# module_instr_reg.net
KiCad netlist of a schematic drawn in EAGLE
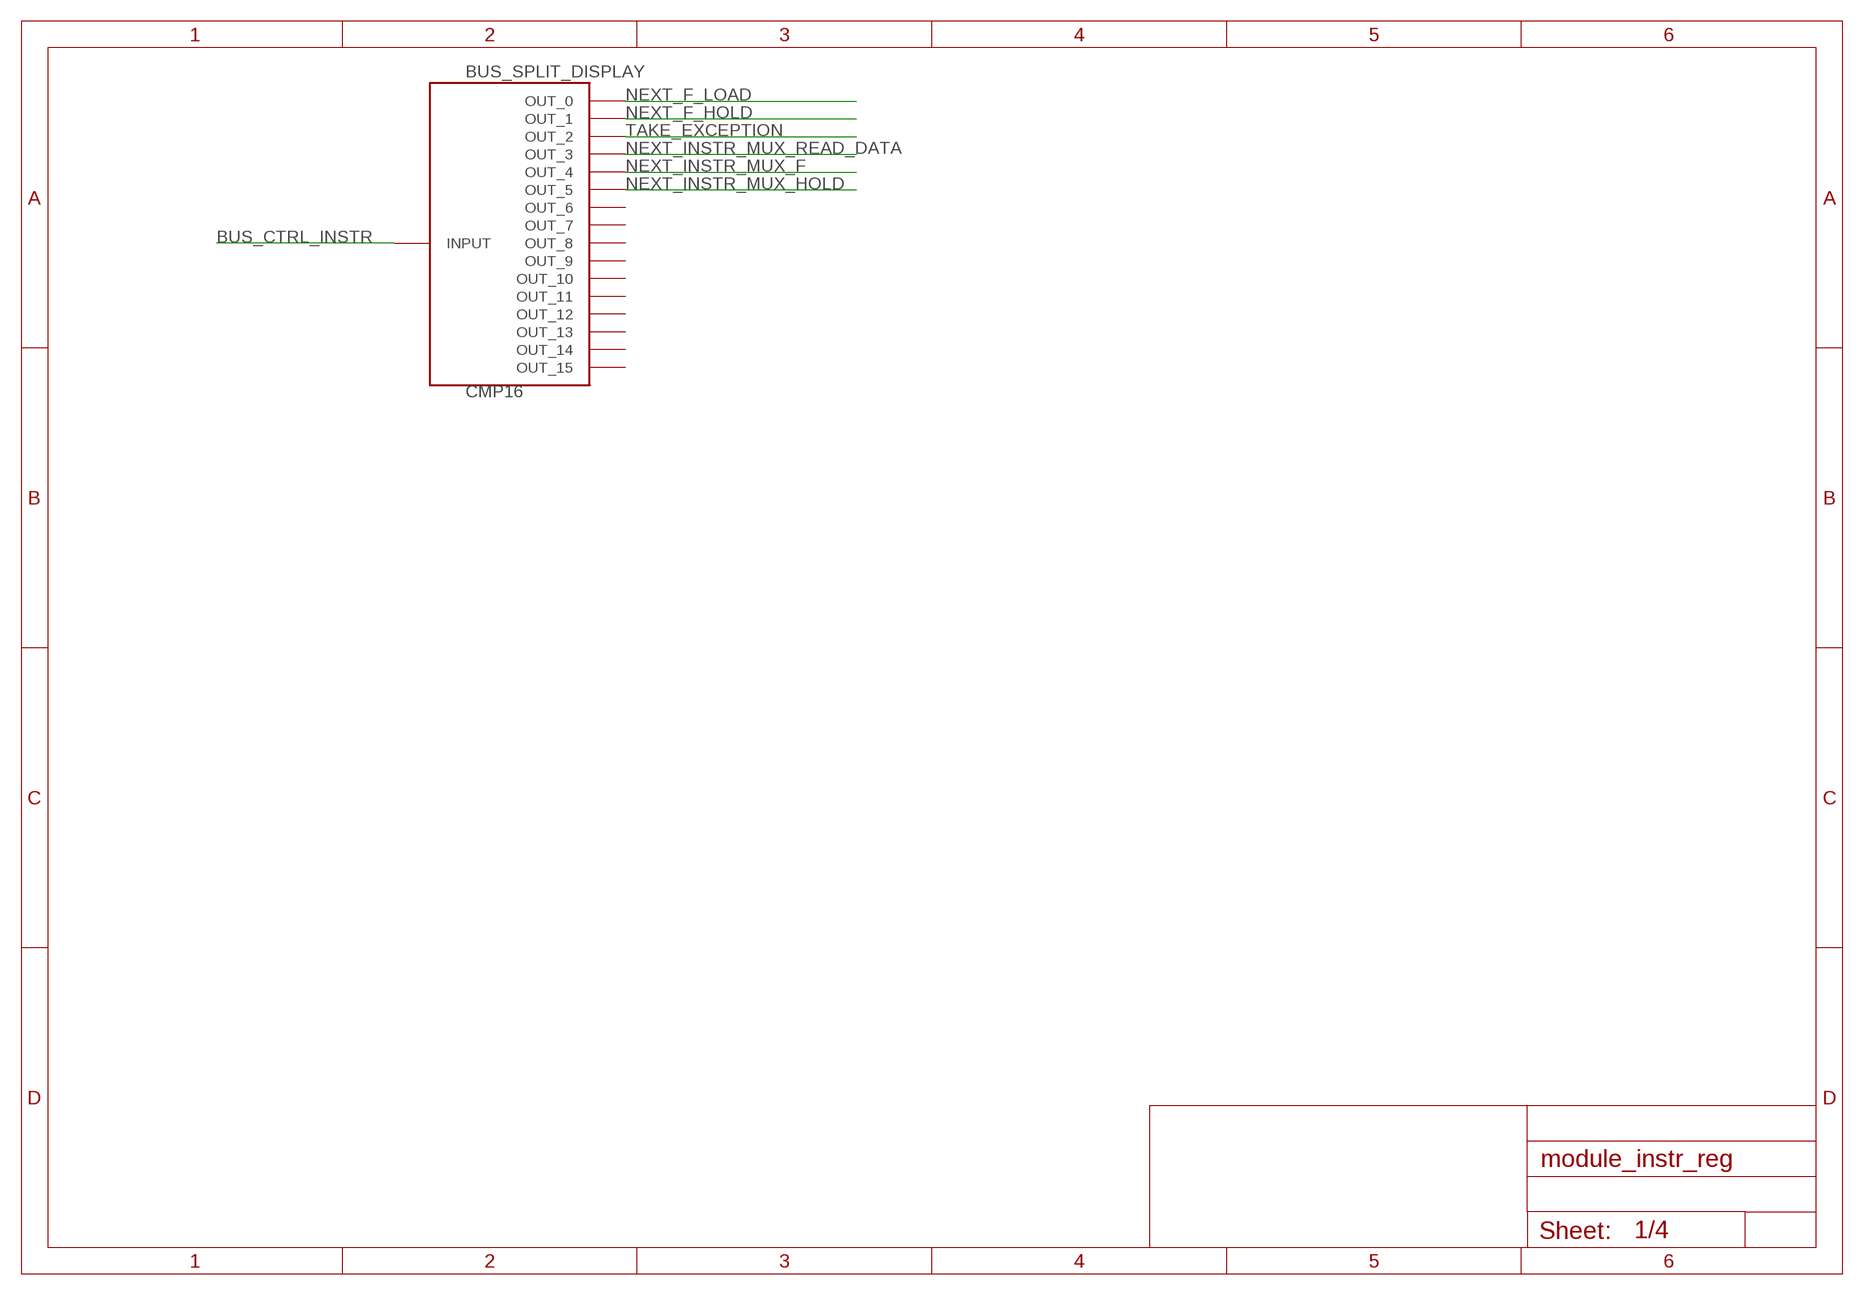
[diagram p0: schematic, sheet 1]
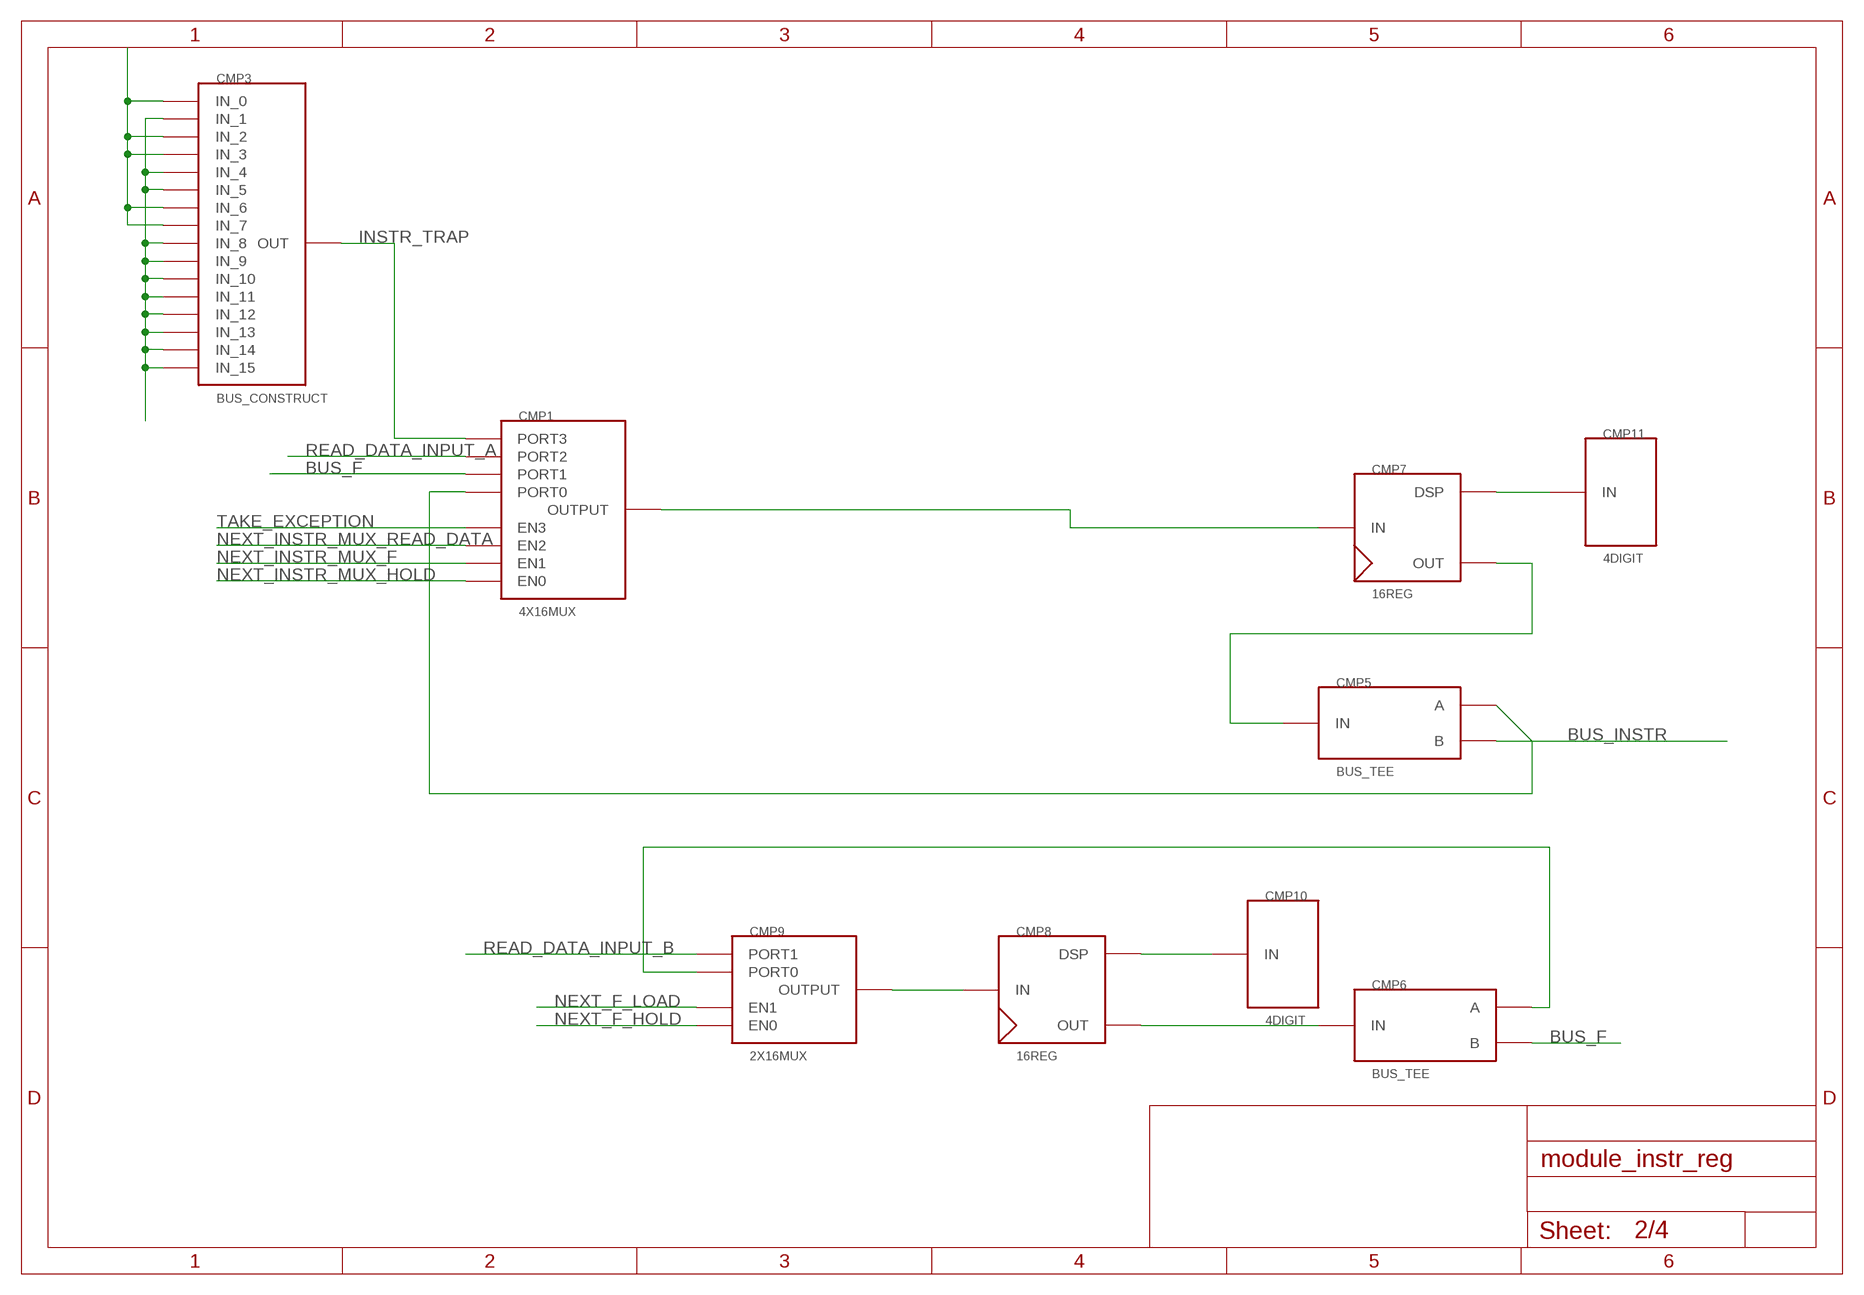
[diagram p1: schematic, sheet 2]
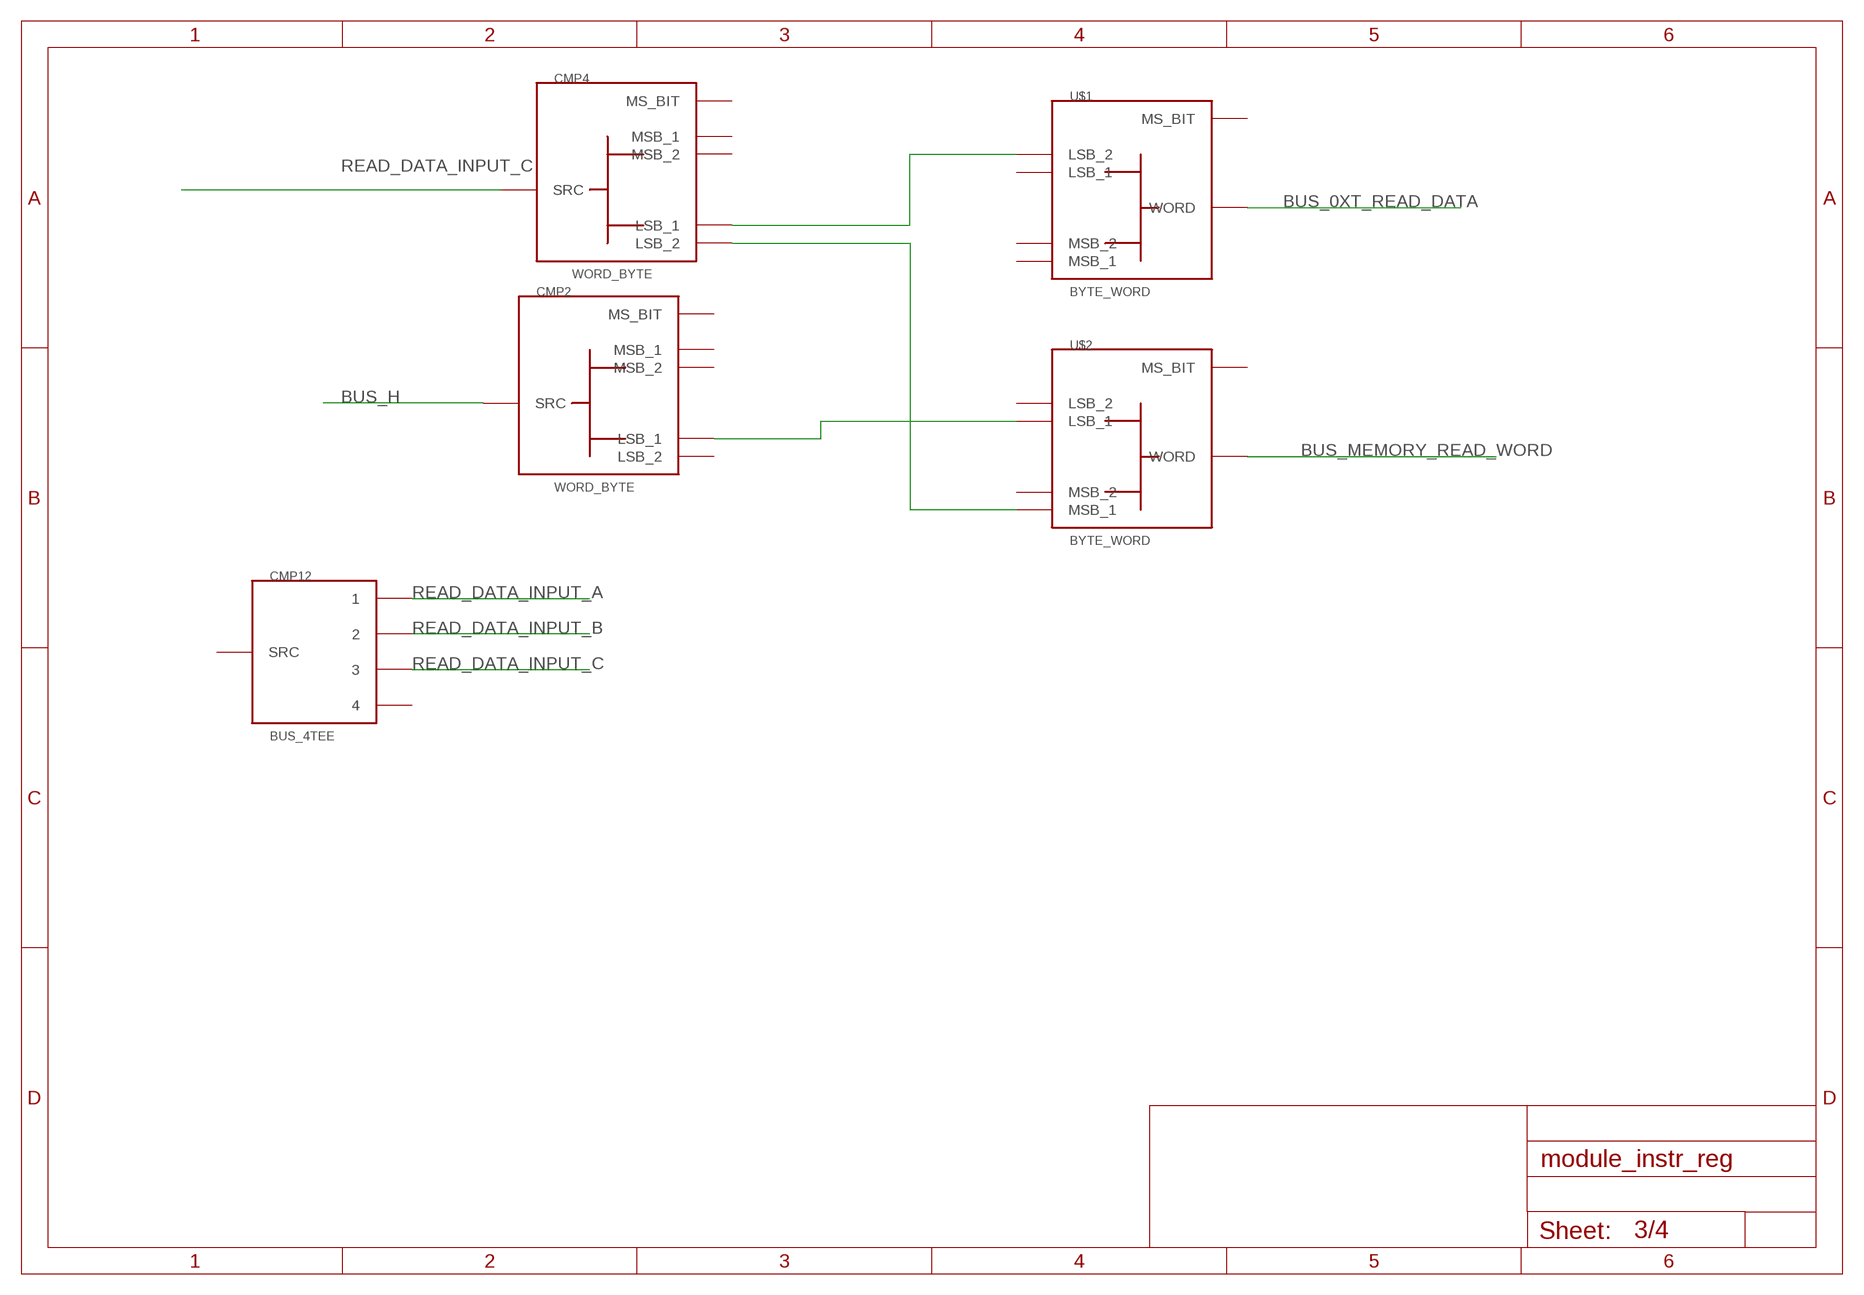
[diagram p2: schematic, sheet 3]
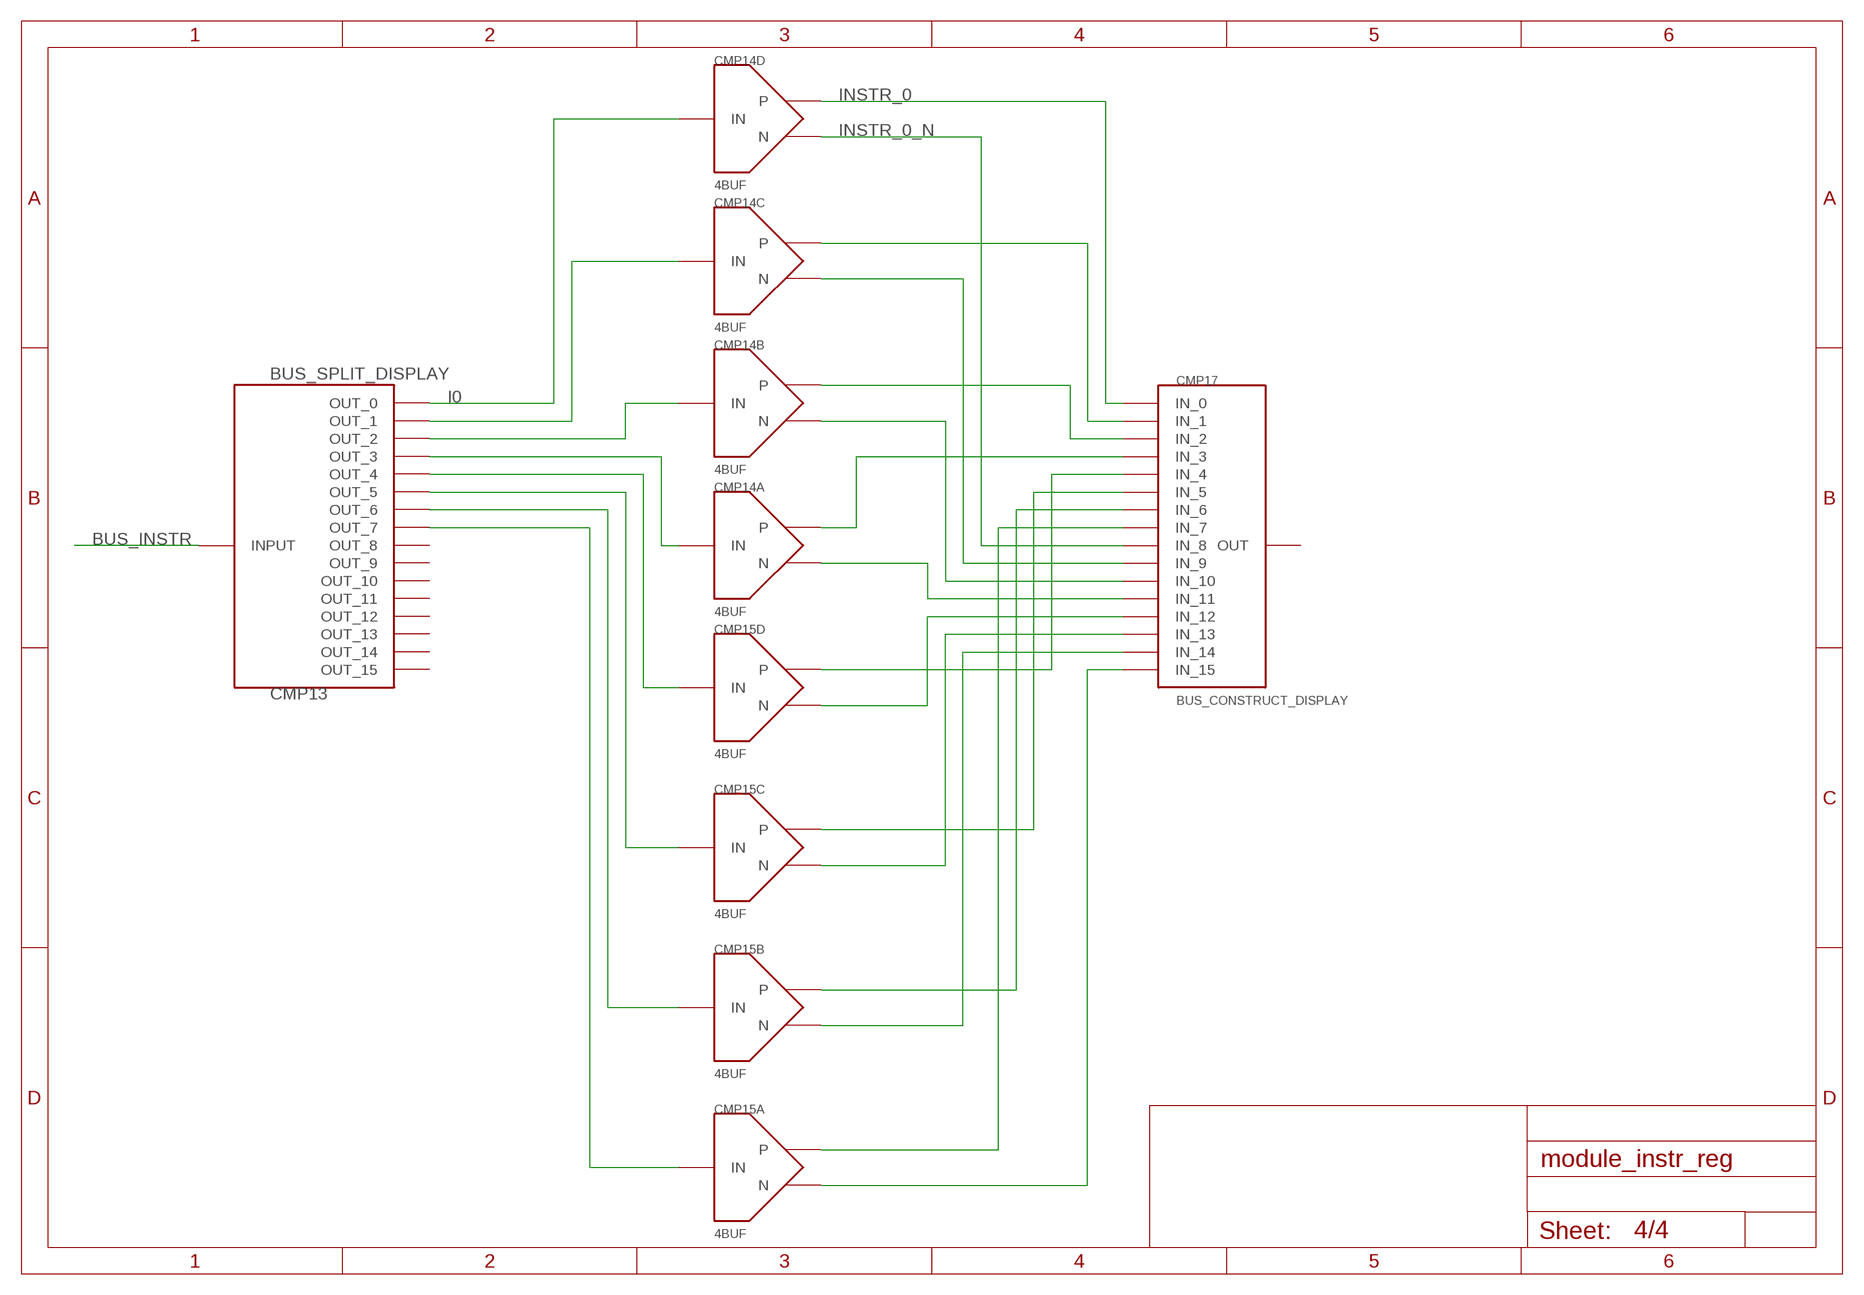
[diagram p3: schematic, sheet 4]

(export (version "E")
  (design (tool "Eeschema 10.0.6"))
  (components
    (comp (ref "CMP16")
      (value "BUS_SPLIT_DISPLAY")
      (footprint "eagle-import:BUS_SPLIT_DISPLAY")
      (libsource (lib "eagle-import") (part "BUS_SPLIT_DISPLAY"))
    )
    (comp (ref "CMP1")
      (value "4X16MUX")
      (footprint "eagle-import:4X16MUX")
      (libsource (lib "eagle-import") (part "4X16MUX"))
    )
    (comp (ref "CMP3")
      (value "BUS_CONSTRUCT")
      (footprint "eagle-import:BUS_SPLIT")
      (libsource (lib "eagle-import") (part "BUS_CONSTRUCT"))
    )
    (comp (ref "CMP5")
      (value "BUS_TEE")
      (footprint "eagle-import:BUS_TEE")
      (libsource (lib "eagle-import") (part "BUS_TEE"))
    )
    (comp (ref "CMP6")
      (value "BUS_TEE")
      (footprint "eagle-import:BUS_TEE")
      (libsource (lib "eagle-import") (part "BUS_TEE"))
    )
    (comp (ref "CMP7")
      (value "16REG")
      (footprint "eagle-import:16REG")
      (libsource (lib "eagle-import") (part "16REG"))
    )
    (comp (ref "CMP8")
      (value "16REG")
      (footprint "eagle-import:16REG")
      (libsource (lib "eagle-import") (part "16REG"))
    )
    (comp (ref "CMP9")
      (value "2X16MUX")
      (footprint "eagle-import:2X16MUX")
      (libsource (lib "eagle-import") (part "2X16MUX"))
    )
    (comp (ref "CMP10")
      (value "4DIGIT")
      (footprint "eagle-import:4DIGIT")
      (libsource (lib "eagle-import") (part "4DIGIT"))
    )
    (comp (ref "CMP11")
      (value "4DIGIT")
      (footprint "eagle-import:4DIGIT")
      (libsource (lib "eagle-import") (part "4DIGIT"))
    )
    (comp (ref "CMP2")
      (value "WORD_BYTE")
      (footprint "eagle-import:WORD_BYTE")
      (libsource (lib "eagle-import") (part "WORD_BYTE"))
    )
    (comp (ref "CMP4")
      (value "WORD_BYTE")
      (footprint "eagle-import:WORD_BYTE")
      (libsource (lib "eagle-import") (part "WORD_BYTE"))
    )
    (comp (ref "CMP12")
      (value "BUS_4TEE")
      (footprint "eagle-import:BUS_4TEE")
      (libsource (lib "eagle-import") (part "BUS_4TEE"))
    )
    (comp (ref "U$1")
      (value "BYTE_WORD")
      (footprint "eagle-import:WORD_BYTE")
      (libsource (lib "eagle-import") (part "BYTE_WORD"))
    )
    (comp (ref "U$2")
      (value "BYTE_WORD")
      (footprint "eagle-import:WORD_BYTE")
      (libsource (lib "eagle-import") (part "BYTE_WORD"))
    )
    (comp (ref "CMP13")
      (value "BUS_SPLIT_DISPLAY")
      (footprint "eagle-import:BUS_SPLIT_DISPLAY")
      (libsource (lib "eagle-import") (part "BUS_SPLIT_DISPLAY"))
    )
    (comp (ref "CMP14")
      (value "4BUF")
      (footprint "eagle-import:4BUF")
      (libsource (lib "eagle-import") (part "4BUF"))
    )
    (comp (ref "CMP15")
      (value "4BUF")
      (footprint "eagle-import:4BUF")
      (libsource (lib "eagle-import") (part "4BUF"))
    )
    (comp (ref "CMP17")
      (value "BUS_CONSTRUCT_DISPLAY")
      (footprint "eagle-import:BUS_SPLIT_DISPLAY")
      (libsource (lib "eagle-import") (part "BUS_CONSTRUCT_DISPLAY"))
    )
  )
  (nets
    (net (code "1") (name "BUS_0XT_READ_DATA") (class "Default")
      (node (ref "U$1") (pin "SRC") (pinfunction "WORD_SRC") (pintype "output"))
    )
    (net (code "2") (name "BUS_CTRL_INSTR") (class "Default")
      (node (ref "CMP16") (pin "INPUT") (pinfunction "INPUT_INPUT") (pintype "input"))
    )
    (net (code "3") (name "BUS_F") (class "Default")
      (node (ref "CMP1") (pin "PORT1") (pinfunction "PORT1_PORT1") (pintype "input"))
      (node (ref "CMP6") (pin "OUTB") (pinfunction "B_OUTB") (pintype "output"))
    )
    (net (code "4") (name "BUS_H") (class "Default")
      (node (ref "CMP2") (pin "SRC") (pinfunction "SRC_SRC") (pintype "input"))
    )
    (net (code "5") (name "BUS_INSTR") (class "Default")
      (node (ref "CMP13") (pin "INPUT") (pinfunction "INPUT_INPUT") (pintype "input"))
      (node (ref "CMP5") (pin "OUTB") (pinfunction "B_OUTB") (pintype "output"))
    )
    (net (code "6") (name "BUS_MEMORY_READ_WORD") (class "Default")
      (node (ref "U$2") (pin "SRC") (pinfunction "WORD_SRC") (pintype "output"))
    )
    (net (code "7") (name "I0") (class "Default")
      (node (ref "CMP13") (pin "P$1") (pinfunction "OUT_0_P$1") (pintype "output"))
      (node (ref "CMP14") (pin "A4") (pinfunction "IN_A4") (pintype "input"))
    )
    (net (code "8") (name "INSTR_0") (class "Default")
      (node (ref "CMP14") (pin "P4") (pinfunction "P_P4") (pintype "output"))
      (node (ref "CMP17") (pin "P$1") (pinfunction "IN_0_P$1") (pintype "input"))
    )
    (net (code "9") (name "INSTR_0_N") (class "Default")
      (node (ref "CMP14") (pin "N4") (pinfunction "N_N4") (pintype "output"))
      (node (ref "CMP17") (pin "P$9") (pinfunction "IN_8_P$9") (pintype "input"))
    )
    (net (code "10") (name "INSTR_TRAP") (class "Default")
      (node (ref "CMP1") (pin "PORT3") (pinfunction "PORT3_PORT3") (pintype "input"))
      (node (ref "CMP3") (pin "INPUT") (pinfunction "OUT_INPUT") (pintype "output"))
    )
    (net (code "11") (name "NEXT_F_HOLD") (class "Default")
      (node (ref "CMP16") (pin "P$2") (pinfunction "OUT_1_P$2") (pintype "output"))
      (node (ref "CMP9") (pin "EN0") (pinfunction "EN0_EN0") (pintype "input"))
    )
    (net (code "12") (name "NEXT_F_LOAD") (class "Default")
      (node (ref "CMP16") (pin "P$1") (pinfunction "OUT_0_P$1") (pintype "output"))
      (node (ref "CMP9") (pin "EN1") (pinfunction "EN1_EN1") (pintype "input"))
    )
    (net (code "13") (name "NEXT_INSTR_MUX_F") (class "Default")
      (node (ref "CMP1") (pin "EN1") (pinfunction "EN1_EN1") (pintype "input"))
      (node (ref "CMP16") (pin "P$5") (pinfunction "OUT_4_P$5") (pintype "output"))
    )
    (net (code "14") (name "NEXT_INSTR_MUX_HOLD") (class "Default")
      (node (ref "CMP1") (pin "EN0") (pinfunction "EN0_EN0") (pintype "input"))
      (node (ref "CMP16") (pin "P$6") (pinfunction "OUT_5_P$6") (pintype "output"))
    )
    (net (code "15") (name "NEXT_INSTR_MUX_READ_DATA") (class "Default")
      (node (ref "CMP1") (pin "EN2") (pinfunction "EN2_EN2") (pintype "input"))
      (node (ref "CMP16") (pin "P$4") (pinfunction "OUT_3_P$4") (pintype "output"))
    )
    (net (code "16") (name "Net-(CMP1-OUTPUT)") (class "Default")
      (node (ref "CMP1") (pin "PORTOUT") (pinfunction "OUTPUT_PORTOUT") (pintype "output"))
      (node (ref "CMP7") (pin "INPUT") (pinfunction "IN_INPUT") (pintype "input"))
    )
    (net (code "17") (name "Net-(CMP2-PadLSB_1)") (class "Default")
      (node (ref "CMP2") (pin "LSB_1") (pinfunction "LSB_1_LSB_1") (pintype "output"))
      (node (ref "U$2") (pin "LSB_1") (pinfunction "LSB_1_LSB_1") (pintype "input"))
    )
    (net (code "18") (name "Net-(CMP3-IN_0)") (class "Default")
      (node (ref "CMP3") (pin "P$1") (pinfunction "IN_0_P$1") (pintype "input"))
      (node (ref "CMP3") (pin "P$3") (pinfunction "IN_2_P$3") (pintype "input"))
      (node (ref "CMP3") (pin "P$4") (pinfunction "IN_3_P$4") (pintype "input"))
      (node (ref "CMP3") (pin "P$7") (pinfunction "IN_6_P$7") (pintype "input"))
      (node (ref "CMP3") (pin "P$8") (pinfunction "IN_7_P$8") (pintype "input"))
    )
    (net (code "19") (name "Net-(CMP3-IN_1)") (class "Default")
      (node (ref "CMP3") (pin "P$10") (pinfunction "IN_9_P$10") (pintype "input"))
      (node (ref "CMP3") (pin "P$11") (pinfunction "IN_10_P$11") (pintype "input"))
      (node (ref "CMP3") (pin "P$12") (pinfunction "IN_11_P$12") (pintype "input"))
      (node (ref "CMP3") (pin "P$13") (pinfunction "IN_12_P$13") (pintype "input"))
      (node (ref "CMP3") (pin "P$14") (pinfunction "IN_13_P$14") (pintype "input"))
      (node (ref "CMP3") (pin "P$15") (pinfunction "IN_14_P$15") (pintype "input"))
      (node (ref "CMP3") (pin "P$16") (pinfunction "IN_15_P$16") (pintype "input"))
      (node (ref "CMP3") (pin "P$2") (pinfunction "IN_1_P$2") (pintype "input"))
      (node (ref "CMP3") (pin "P$5") (pinfunction "IN_4_P$5") (pintype "input"))
      (node (ref "CMP3") (pin "P$6") (pinfunction "IN_5_P$6") (pintype "input"))
      (node (ref "CMP3") (pin "P$9") (pinfunction "IN_8_P$9") (pintype "input"))
    )
    (net (code "20") (name "Net-(CMP4-PadLSB_1)") (class "Default")
      (node (ref "CMP4") (pin "LSB_1") (pinfunction "LSB_1_LSB_1") (pintype "output"))
      (node (ref "U$1") (pin "LSB_2") (pinfunction "LSB_2_LSB_2") (pintype "input"))
    )
    (net (code "21") (name "Net-(CMP4-PadLSB_2)") (class "Default")
      (node (ref "CMP4") (pin "LSB_2") (pinfunction "LSB_2_LSB_2") (pintype "output"))
      (node (ref "U$2") (pin "MSB_1") (pinfunction "MSB_1_MSB_1") (pintype "input"))
    )
    (net (code "22") (name "Net-(CMP5-A)") (class "Default")
      (node (ref "CMP1") (pin "PORT0") (pinfunction "PORT0_PORT0") (pintype "input"))
      (node (ref "CMP5") (pin "OUT_A") (pinfunction "A_OUT_A") (pintype "output"))
    )
    (net (code "23") (name "Net-(CMP5-IN)") (class "Default")
      (node (ref "CMP5") (pin "INPUT") (pinfunction "IN_INPUT") (pintype "input"))
      (node (ref "CMP7") (pin "OUT") (pinfunction "OUT_OUT") (pintype "output"))
    )
    (net (code "24") (name "Net-(CMP6-A)") (class "Default")
      (node (ref "CMP6") (pin "OUT_A") (pinfunction "A_OUT_A") (pintype "output"))
      (node (ref "CMP9") (pin "PORT0") (pinfunction "PORT0_PORT0") (pintype "input"))
    )
    (net (code "25") (name "Net-(CMP6-IN)") (class "Default")
      (node (ref "CMP6") (pin "INPUT") (pinfunction "IN_INPUT") (pintype "input"))
      (node (ref "CMP8") (pin "OUT") (pinfunction "OUT_OUT") (pintype "output"))
    )
    (net (code "26") (name "Net-(CMP8-IN)") (class "Default")
      (node (ref "CMP8") (pin "INPUT") (pinfunction "IN_INPUT") (pintype "input"))
      (node (ref "CMP9") (pin "OUT") (pinfunction "OUTPUT_OUT") (pintype "output"))
    )
    (net (code "27") (name "Net-(CMP10-IN)") (class "Default")
      (node (ref "CMP10") (pin "P$1") (pinfunction "IN_P$1") (pintype "input"))
      (node (ref "CMP8") (pin "DISPLAY") (pinfunction "DSP_DISPLAY") (pintype "output"))
    )
    (net (code "28") (name "Net-(CMP11-IN)") (class "Default")
      (node (ref "CMP11") (pin "P$1") (pinfunction "IN_P$1") (pintype "input"))
      (node (ref "CMP7") (pin "DISPLAY") (pinfunction "DSP_DISPLAY") (pintype "output"))
    )
    (net (code "29") (name "Net-(CMP13-OUT_1)") (class "Default")
      (node (ref "CMP13") (pin "P$2") (pinfunction "OUT_1_P$2") (pintype "output"))
      (node (ref "CMP14") (pin "A3") (pinfunction "IN_A3") (pintype "input"))
    )
    (net (code "30") (name "Net-(CMP13-OUT_2)") (class "Default")
      (node (ref "CMP13") (pin "P$3") (pinfunction "OUT_2_P$3") (pintype "output"))
      (node (ref "CMP14") (pin "A2") (pinfunction "IN_A2") (pintype "input"))
    )
    (net (code "31") (name "Net-(CMP13-OUT_3)") (class "Default")
      (node (ref "CMP13") (pin "P$4") (pinfunction "OUT_3_P$4") (pintype "output"))
      (node (ref "CMP14") (pin "A1") (pinfunction "IN_A1") (pintype "input"))
    )
    (net (code "32") (name "Net-(CMP13-OUT_4)") (class "Default")
      (node (ref "CMP13") (pin "P$5") (pinfunction "OUT_4_P$5") (pintype "output"))
      (node (ref "CMP15") (pin "A4") (pinfunction "IN_A4") (pintype "input"))
    )
    (net (code "33") (name "Net-(CMP13-OUT_5)") (class "Default")
      (node (ref "CMP13") (pin "P$6") (pinfunction "OUT_5_P$6") (pintype "output"))
      (node (ref "CMP15") (pin "A3") (pinfunction "IN_A3") (pintype "input"))
    )
    (net (code "34") (name "Net-(CMP13-OUT_6)") (class "Default")
      (node (ref "CMP13") (pin "P$7") (pinfunction "OUT_6_P$7") (pintype "output"))
      (node (ref "CMP15") (pin "A2") (pinfunction "IN_A2") (pintype "input"))
    )
    (net (code "35") (name "Net-(CMP13-OUT_7)") (class "Default")
      (node (ref "CMP13") (pin "P$8") (pinfunction "OUT_7_P$8") (pintype "output"))
      (node (ref "CMP15") (pin "A1") (pinfunction "IN_A1") (pintype "input"))
    )
    (net (code "36") (name "Net-(CMP14A-N)") (class "Default")
      (node (ref "CMP14") (pin "N1") (pinfunction "N_N1") (pintype "output"))
      (node (ref "CMP17") (pin "P$12") (pinfunction "IN_11_P$12") (pintype "input"))
    )
    (net (code "37") (name "Net-(CMP14A-P)") (class "Default")
      (node (ref "CMP14") (pin "P1") (pinfunction "P_P1") (pintype "output"))
      (node (ref "CMP17") (pin "P$4") (pinfunction "IN_3_P$4") (pintype "input"))
    )
    (net (code "38") (name "Net-(CMP14B-N)") (class "Default")
      (node (ref "CMP14") (pin "N2") (pinfunction "N_N2") (pintype "output"))
      (node (ref "CMP17") (pin "P$11") (pinfunction "IN_10_P$11") (pintype "input"))
    )
    (net (code "39") (name "Net-(CMP14B-P)") (class "Default")
      (node (ref "CMP14") (pin "P2") (pinfunction "P_P2") (pintype "output"))
      (node (ref "CMP17") (pin "P$3") (pinfunction "IN_2_P$3") (pintype "input"))
    )
    (net (code "40") (name "Net-(CMP14C-N)") (class "Default")
      (node (ref "CMP14") (pin "N3") (pinfunction "N_N3") (pintype "output"))
      (node (ref "CMP17") (pin "P$10") (pinfunction "IN_9_P$10") (pintype "input"))
    )
    (net (code "41") (name "Net-(CMP14C-P)") (class "Default")
      (node (ref "CMP14") (pin "P3") (pinfunction "P_P3") (pintype "output"))
      (node (ref "CMP17") (pin "P$2") (pinfunction "IN_1_P$2") (pintype "input"))
    )
    (net (code "42") (name "Net-(CMP15A-N)") (class "Default")
      (node (ref "CMP15") (pin "N1") (pinfunction "N_N1") (pintype "output"))
      (node (ref "CMP17") (pin "P$16") (pinfunction "IN_15_P$16") (pintype "input"))
    )
    (net (code "43") (name "Net-(CMP15A-P)") (class "Default")
      (node (ref "CMP15") (pin "P1") (pinfunction "P_P1") (pintype "output"))
      (node (ref "CMP17") (pin "P$8") (pinfunction "IN_7_P$8") (pintype "input"))
    )
    (net (code "44") (name "Net-(CMP15B-N)") (class "Default")
      (node (ref "CMP15") (pin "N2") (pinfunction "N_N2") (pintype "output"))
      (node (ref "CMP17") (pin "P$15") (pinfunction "IN_14_P$15") (pintype "input"))
    )
    (net (code "45") (name "Net-(CMP15B-P)") (class "Default")
      (node (ref "CMP15") (pin "P2") (pinfunction "P_P2") (pintype "output"))
      (node (ref "CMP17") (pin "P$7") (pinfunction "IN_6_P$7") (pintype "input"))
    )
    (net (code "46") (name "Net-(CMP15C-N)") (class "Default")
      (node (ref "CMP15") (pin "N3") (pinfunction "N_N3") (pintype "output"))
      (node (ref "CMP17") (pin "P$14") (pinfunction "IN_13_P$14") (pintype "input"))
    )
    (net (code "47") (name "Net-(CMP15C-P)") (class "Default")
      (node (ref "CMP15") (pin "P3") (pinfunction "P_P3") (pintype "output"))
      (node (ref "CMP17") (pin "P$6") (pinfunction "IN_5_P$6") (pintype "input"))
    )
    (net (code "48") (name "Net-(CMP15D-N)") (class "Default")
      (node (ref "CMP15") (pin "N4") (pinfunction "N_N4") (pintype "output"))
      (node (ref "CMP17") (pin "P$13") (pinfunction "IN_12_P$13") (pintype "input"))
    )
    (net (code "49") (name "Net-(CMP15D-P)") (class "Default")
      (node (ref "CMP15") (pin "P4") (pinfunction "P_P4") (pintype "output"))
      (node (ref "CMP17") (pin "P$5") (pinfunction "IN_4_P$5") (pintype "input"))
    )
    (net (code "50") (name "READ_DATA_INPUT_A") (class "Default")
      (node (ref "CMP1") (pin "PORT2") (pinfunction "PORT2_PORT2") (pintype "input"))
      (node (ref "CMP12") (pin "1") (pinfunction "1_1") (pintype "output"))
    )
    (net (code "51") (name "READ_DATA_INPUT_B") (class "Default")
      (node (ref "CMP12") (pin "2") (pinfunction "2_2") (pintype "output"))
      (node (ref "CMP9") (pin "PORT1") (pinfunction "PORT1_PORT1") (pintype "input"))
    )
    (net (code "52") (name "READ_DATA_INPUT_C") (class "Default")
      (node (ref "CMP12") (pin "3") (pinfunction "3_3") (pintype "output"))
      (node (ref "CMP4") (pin "SRC") (pinfunction "SRC_SRC") (pintype "input"))
    )
    (net (code "53") (name "TAKE_EXCEPTION") (class "Default")
      (node (ref "CMP1") (pin "EN3") (pinfunction "EN3_EN3") (pintype "input"))
      (node (ref "CMP16") (pin "P$3") (pinfunction "OUT_2_P$3") (pintype "output"))
    )
    (net (code "54") (name "unconnected-(CMP2-PadLSB_2)") (class "Default")
      (node (ref "CMP2") (pin "LSB_2") (pinfunction "LSB_2_LSB_2") (pintype "output"))
    )
    (net (code "55") (name "unconnected-(CMP2-PadMSB_1)") (class "Default")
      (node (ref "CMP2") (pin "MSB_1") (pinfunction "MSB_1_MSB_1") (pintype "output"))
    )
    (net (code "56") (name "unconnected-(CMP2-PadMSB_2)") (class "Default")
      (node (ref "CMP2") (pin "MSB_2") (pinfunction "MSB_2_MSB_2") (pintype "output"))
    )
    (net (code "57") (name "unconnected-(CMP2-PadMS_BIT)") (class "Default")
      (node (ref "CMP2") (pin "MS_BIT") (pinfunction "MS_BIT_MS_BIT") (pintype "output"))
    )
    (net (code "58") (name "unconnected-(CMP4-PadMSB_1)") (class "Default")
      (node (ref "CMP4") (pin "MSB_1") (pinfunction "MSB_1_MSB_1") (pintype "output"))
    )
    (net (code "59") (name "unconnected-(CMP4-PadMSB_2)") (class "Default")
      (node (ref "CMP4") (pin "MSB_2") (pinfunction "MSB_2_MSB_2") (pintype "output"))
    )
    (net (code "60") (name "unconnected-(CMP4-PadMS_BIT)") (class "Default")
      (node (ref "CMP4") (pin "MS_BIT") (pinfunction "MS_BIT_MS_BIT") (pintype "output"))
    )
    (net (code "61") (name "unconnected-(CMP12-Pad4)") (class "Default")
      (node (ref "CMP12") (pin "4") (pinfunction "4_4") (pintype "output"))
    )
    (net (code "62") (name "unconnected-(CMP12-PadSRC)") (class "Default")
      (node (ref "CMP12") (pin "SRC") (pinfunction "SRC_SRC") (pintype "input"))
    )
    (net (code "63") (name "unconnected-(CMP13-OUT_8-PadP$9)") (class "Default")
      (node (ref "CMP13") (pin "P$9") (pinfunction "OUT_8_P$9") (pintype "output"))
    )
    (net (code "64") (name "unconnected-(CMP13-OUT_9-PadP$10)") (class "Default")
      (node (ref "CMP13") (pin "P$10") (pinfunction "OUT_9_P$10") (pintype "output"))
    )
    (net (code "65") (name "unconnected-(CMP13-OUT_10-PadP$11)") (class "Default")
      (node (ref "CMP13") (pin "P$11") (pinfunction "OUT_10_P$11") (pintype "output"))
    )
    (net (code "66") (name "unconnected-(CMP13-OUT_11-PadP$12)") (class "Default")
      (node (ref "CMP13") (pin "P$12") (pinfunction "OUT_11_P$12") (pintype "output"))
    )
    (net (code "67") (name "unconnected-(CMP13-OUT_12-PadP$13)") (class "Default")
      (node (ref "CMP13") (pin "P$13") (pinfunction "OUT_12_P$13") (pintype "output"))
    )
    (net (code "68") (name "unconnected-(CMP13-OUT_13-PadP$14)") (class "Default")
      (node (ref "CMP13") (pin "P$14") (pinfunction "OUT_13_P$14") (pintype "output"))
    )
    (net (code "69") (name "unconnected-(CMP13-OUT_14-PadP$15)") (class "Default")
      (node (ref "CMP13") (pin "P$15") (pinfunction "OUT_14_P$15") (pintype "output"))
    )
    (net (code "70") (name "unconnected-(CMP13-OUT_15-PadP$16)") (class "Default")
      (node (ref "CMP13") (pin "P$16") (pinfunction "OUT_15_P$16") (pintype "output"))
    )
    (net (code "71") (name "unconnected-(CMP16-OUT_6-PadP$7)") (class "Default")
      (node (ref "CMP16") (pin "P$7") (pinfunction "OUT_6_P$7") (pintype "output"))
    )
    (net (code "72") (name "unconnected-(CMP16-OUT_7-PadP$8)") (class "Default")
      (node (ref "CMP16") (pin "P$8") (pinfunction "OUT_7_P$8") (pintype "output"))
    )
    (net (code "73") (name "unconnected-(CMP16-OUT_8-PadP$9)") (class "Default")
      (node (ref "CMP16") (pin "P$9") (pinfunction "OUT_8_P$9") (pintype "output"))
    )
    (net (code "74") (name "unconnected-(CMP16-OUT_9-PadP$10)") (class "Default")
      (node (ref "CMP16") (pin "P$10") (pinfunction "OUT_9_P$10") (pintype "output"))
    )
    (net (code "75") (name "unconnected-(CMP16-OUT_10-PadP$11)") (class "Default")
      (node (ref "CMP16") (pin "P$11") (pinfunction "OUT_10_P$11") (pintype "output"))
    )
    (net (code "76") (name "unconnected-(CMP16-OUT_11-PadP$12)") (class "Default")
      (node (ref "CMP16") (pin "P$12") (pinfunction "OUT_11_P$12") (pintype "output"))
    )
    (net (code "77") (name "unconnected-(CMP16-OUT_12-PadP$13)") (class "Default")
      (node (ref "CMP16") (pin "P$13") (pinfunction "OUT_12_P$13") (pintype "output"))
    )
    (net (code "78") (name "unconnected-(CMP16-OUT_13-PadP$14)") (class "Default")
      (node (ref "CMP16") (pin "P$14") (pinfunction "OUT_13_P$14") (pintype "output"))
    )
    (net (code "79") (name "unconnected-(CMP16-OUT_14-PadP$15)") (class "Default")
      (node (ref "CMP16") (pin "P$15") (pinfunction "OUT_14_P$15") (pintype "output"))
    )
    (net (code "80") (name "unconnected-(CMP16-OUT_15-PadP$16)") (class "Default")
      (node (ref "CMP16") (pin "P$16") (pinfunction "OUT_15_P$16") (pintype "output"))
    )
    (net (code "81") (name "unconnected-(CMP17-OUT-PadINPUT)") (class "Default")
      (node (ref "CMP17") (pin "INPUT") (pinfunction "OUT_INPUT") (pintype "output"))
    )
    (net (code "82") (name "unconnected-(U$1-PadLSB_1)") (class "Default")
      (node (ref "U$1") (pin "LSB_1") (pinfunction "LSB_1_LSB_1") (pintype "input"))
    )
    (net (code "83") (name "unconnected-(U$1-PadMSB_1)") (class "Default")
      (node (ref "U$1") (pin "MSB_1") (pinfunction "MSB_1_MSB_1") (pintype "input"))
    )
    (net (code "84") (name "unconnected-(U$1-PadMSB_2)") (class "Default")
      (node (ref "U$1") (pin "MSB_2") (pinfunction "MSB_2_MSB_2") (pintype "input"))
    )
    (net (code "85") (name "unconnected-(U$1-PadMS_BIT)") (class "Default")
      (node (ref "U$1") (pin "MS_BIT") (pinfunction "MS_BIT_MS_BIT") (pintype "output"))
    )
    (net (code "86") (name "unconnected-(U$2-PadLSB_2)") (class "Default")
      (node (ref "U$2") (pin "LSB_2") (pinfunction "LSB_2_LSB_2") (pintype "input"))
    )
    (net (code "87") (name "unconnected-(U$2-PadMSB_2)") (class "Default")
      (node (ref "U$2") (pin "MSB_2") (pinfunction "MSB_2_MSB_2") (pintype "input"))
    )
    (net (code "88") (name "unconnected-(U$2-PadMS_BIT)") (class "Default")
      (node (ref "U$2") (pin "MS_BIT") (pinfunction "MS_BIT_MS_BIT") (pintype "output"))
    )
  )
)
